# Myespsch1.net
KiCad netlist of a schematic drawn in Altium Designer
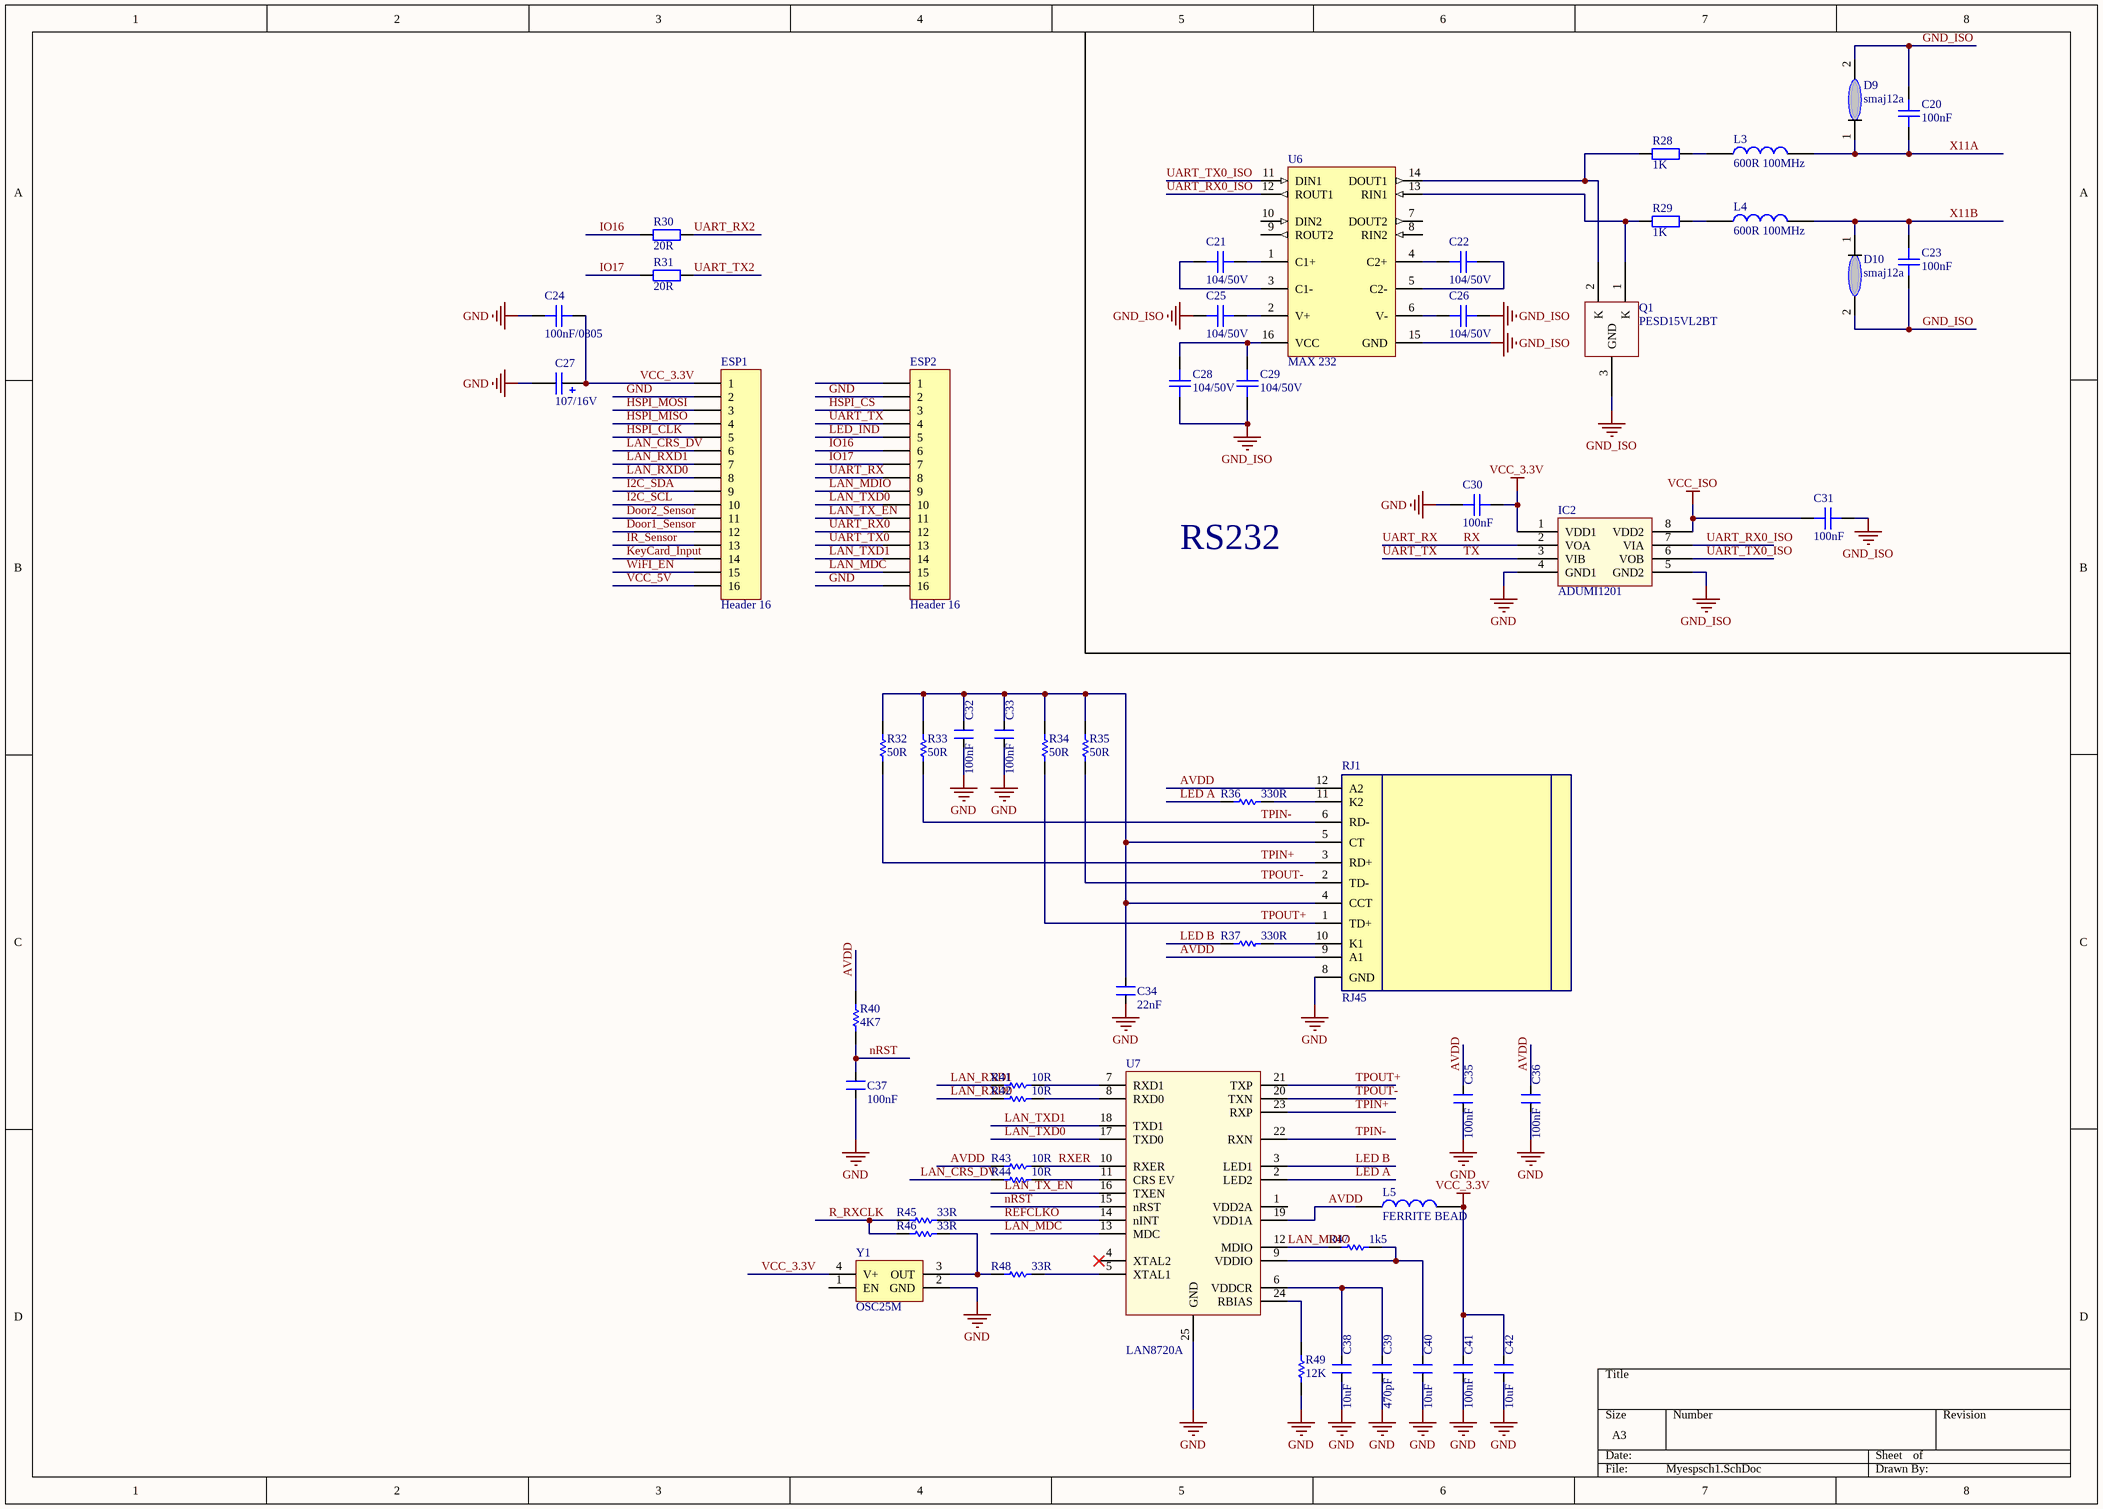
[diagram p0: Myespsch1.SchDoc]

(export (version "E")
  (design (tool "Eeschema 10.0.6"))
  (components
    (comp (ref "C20")
      (value "100nF")
      (footprint "CAPC-0603 (1608)")
      (fields (field (name "MPN") "C0603C104K5RACTU"))
      (libsource (lib "BYTECH_HW_LIB_2019 (1)") (part "C0603C104K5RACTU"))
    )
    (comp (ref "C21")
      (value "104/50V")
      (footprint "CAPC-0603 (1608)")
      (description "CAP CER 0.1uF 50V 10% X7R 0603")
      (fields (field (name "MPN") "C0603C104K5RACTU"))
      (libsource (lib "BYTECH_HW_LIB_2019 (1)") (part "C0603C104K5RACTU"))
    )
    (comp (ref "C22")
      (value "104/50V")
      (footprint "CAPC-0603 (1608)")
      (description "CAP CER 0.1uF 50V 10% X7R 0603")
      (fields (field (name "MPN") "C0603C104K5RACTU"))
      (libsource (lib "BYTECH_HW_LIB_2019 (1)") (part "C0603C104K5RACTU"))
    )
    (comp (ref "C23")
      (value "100nF")
      (footprint "CAPC-0603 (1608)")
      (fields (field (name "MPN") "C0603C104K5RACTU"))
      (libsource (lib "BYTECH_HW_LIB_2019 (1)") (part "C0603C104K5RACTU"))
    )
    (comp (ref "C24")
      (value "100nF/0805")
      (footprint "CAPC-0805 (2012)")
      (description "CAP CER 2.2uF 10% 10V X5R 0805")
      (fields (field (name "MPN") "0805C225K8PAC7800"))
      (libsource (lib "BYTECH_HW_LIB_2019 (1)") (part "0805C225K8PAC7800"))
    )
    (comp (ref "C25")
      (value "104/50V")
      (footprint "CAPC-0603 (1608)")
      (description "CAP CER 0.1uF 50V 10% X7R 0603")
      (fields (field (name "MPN") "C0603C104K5RACTU"))
      (libsource (lib "BYTECH_HW_LIB_2019 (1)") (part "C0603C104K5RACTU"))
    )
    (comp (ref "C26")
      (value "104/50V")
      (footprint "CAPC-0603 (1608)")
      (description "CAP CER 0.1uF 50V 10% X7R 0603")
      (fields (field (name "MPN") "C0603C104K5RACTU"))
      (libsource (lib "BYTECH_HW_LIB_2019 (1)") (part "C0603C104K5RACTU"))
    )
    (comp (ref "C27")
      (value "107/16V")
      (footprint "CAP_TANTAL_2917(7343-31)")
      (description "CAP TANT 100uF 16V 10% 2917")
      (fields (field (name "MPN") "TAJD107K016RNJ"))
      (libsource (lib "BYTECH_HW_LIB_2019 (1)") (part "TAJD107K016RNJ"))
    )
    (comp (ref "C28")
      (value "104/50V")
      (footprint "CAPC-0603 (1608)")
      (description "CAP CER 0.1uF 50V 10% X7R 0603")
      (fields (field (name "MPN") "C0603C104K5RACTU"))
      (libsource (lib "BYTECH_HW_LIB_2019 (1)") (part "C0603C104K5RACTU"))
    )
    (comp (ref "C29")
      (value "104/50V")
      (footprint "CAPC-0603 (1608)")
      (description "CAP CER 0.1uF 50V 10% X7R 0603")
      (fields (field (name "MPN") "C0603C104K5RACTU"))
      (libsource (lib "BYTECH_HW_LIB_2019 (1)") (part "C0603C104K5RACTU"))
    )
    (comp (ref "C30")
      (value "100nF")
      (footprint "CAPC-0603 (1608)")
      (fields (field (name "MPN") "C0603C104K5RACTU"))
      (libsource (lib "BYTECH_HW_LIB_2019 (1)") (part "C0603C104K5RACTU"))
    )
    (comp (ref "C31")
      (value "100nF")
      (footprint "CAPC-0603 (1608)")
      (fields (field (name "MPN") "C0603C104K5RACTU"))
      (libsource (lib "BYTECH_HW_LIB_2019 (1)") (part "C0603C104K5RACTU"))
    )
    (comp (ref "C32")
      (value "100nF")
      (footprint "CAPC-0805 (2012)")
      (description "CERAMIC CAP 0805")
      (libsource (lib "lpson") (part "CAP CERA 0805"))
    )
    (comp (ref "C33")
      (value "100nF")
      (footprint "CAPC-0805 (2012)")
      (description "CERAMIC CAP 0805")
      (libsource (lib "lpson") (part "CAP CERA 0805"))
    )
    (comp (ref "C34")
      (value "22nF")
      (footprint "CAPC-0805 (2012)")
      (description "CERAMIC CAP 0805")
      (libsource (lib "lpson") (part "CAP CERA 0805"))
    )
    (comp (ref "C35")
      (value "100nF")
      (footprint "CAPC-0805 (2012)")
      (description "CERAMIC CAP 0805")
      (libsource (lib "lpson") (part "CAP CERA 0805"))
    )
    (comp (ref "C36")
      (value "100nF")
      (footprint "CAPC-0805 (2012)")
      (description "CERAMIC CAP 0805")
      (libsource (lib "lpson") (part "CAP CERA 0805"))
    )
    (comp (ref "C37")
      (value "100nF")
      (footprint "RESC-0805 (2012)")
      (description "CERAMIC CAP 0805")
      (libsource (lib "lpson") (part "CAP CERA 0805"))
    )
    (comp (ref "C38")
      (value "10uF")
      (footprint "CAPC-0805 (2012)")
      (description "CERAMIC CAP 0805")
      (libsource (lib "lpson") (part "CAP CERA 0805"))
    )
    (comp (ref "C39")
      (value "470pF")
      (footprint "CAPC-0805 (2012)")
      (description "CERAMIC CAP 0805")
      (libsource (lib "lpson") (part "CAP CERA 0805"))
    )
    (comp (ref "C40")
      (value "10uF")
      (footprint "CAPC-0805 (2012)")
      (description "CERAMIC CAP 0805")
      (libsource (lib "lpson") (part "CAP CERA 0805"))
    )
    (comp (ref "C41")
      (value "100nF")
      (footprint "CAPC-0805 (2012)")
      (description "CERAMIC CAP 0805")
      (libsource (lib "lpson") (part "CAP CERA 0805"))
    )
    (comp (ref "C42")
      (value "10uF")
      (footprint "CAPC-0805 (2012)")
      (description "CERAMIC CAP 0805")
      (libsource (lib "lpson") (part "CAP CERA 0805"))
    )
    (comp (ref "D9")
      (value "smaj12a")
      (footprint "DIODE_DO214AC_SMA")
      (libsource (lib "Schlib1") (part "smaj12a"))
    )
    (comp (ref "D10")
      (value "smaj12a")
      (footprint "DIODE_DO214AC_SMA")
      (libsource (lib "") (part "smaj12a_1"))
    )
    (comp (ref "ESP1")
      (value "Header 16")
      (footprint "HDR1X16")
      (description "Header, 16-Pin")
      (fields (field (name "PUBLISHER") "Altium Limited"))
      (libsource (lib "My Library") (part "Header 16"))
    )
    (comp (ref "ESP2")
      (value "Header 16")
      (footprint "HDR1X16")
      (description "Header, 16-Pin")
      (fields (field (name "PUBLISHER") "Altium Limited"))
      (libsource (lib "My Library") (part "Header 16"))
    )
    (comp (ref "IC2") (value "ADUMI1201") (footprint "SOIC-8") (libsource (lib "Schlib1") (part "ADUMI1201")))
    (comp (ref "L3")
      (value "600R 100MHz")
      (footprint "IND-0603 (1608)")
      (description "FIXED IND 2.2UH 700MA 375 MOHM")
      (fields (field (name "MPN") "LQM18PN2R2MFHD") (field (name "MFR") "Murata Electronics"))
      (libsource (lib "BYTECH_HW_LIB_2019 (1)") (part "LQM18PN2R2MFHD"))
    )
    (comp (ref "L4")
      (value "600R 100MHz")
      (footprint "IND-0603 (1608)")
      (description "FIXED IND 2.2UH 700MA 375 MOHM")
      (fields (field (name "MPN") "LQM18PN2R2MFHD") (field (name "MFR") "Murata Electronics"))
      (libsource (lib "BYTECH_HW_LIB_2019 (1)") (part "LQM18PN2R2MFHD"))
    )
    (comp (ref "L5")
      (value "FERRITE BEAD")
      (footprint "IND-0805 (2012)")
      (description "IND-FERRITE BEAD 600 OHM 1LN 0805")
      (fields (field (name "MPN") "742792042"))
      (libsource (lib "BYTECH_HW_LIB_2019") (part "742792042"))
    )
    (comp (ref "Q1") (value "PESD15VL2BT") (footprint "SOT23") (libsource (lib "P1") (part "PESD15VL2BT")))
    (comp (ref "R28")
      (value "1K")
      (footprint "RESC-0603 (1608)")
      (description "RES SMD 4.7K OHM 1% 1/10W 0603")
      (fields (field (name "MPN") "RC0603FR-074K7L"))
      (libsource (lib "BYTECH_HW_LIB_2019 (1)") (part "RC0603FR-074K7L"))
    )
    (comp (ref "R29")
      (value "1K")
      (footprint "RESC-0603 (1608)")
      (description "RES SMD 4.7K OHM 1% 1/10W 0603")
      (fields (field (name "MPN") "RC0603FR-074K7L"))
      (libsource (lib "BYTECH_HW_LIB_2019 (1)") (part "RC0603FR-074K7L"))
    )
    (comp (ref "R30")
      (value "20R")
      (footprint "RESC-0603 (1608)")
      (description "RES SMD 20 OHM 1% 1/10W 0603")
      (fields (field (name "MPN") "CRCW060320R0FKEA"))
      (libsource (lib "BYTECH_HW_LIB_2019 (1)") (part "CRCW060320R0FKEA"))
    )
    (comp (ref "R31")
      (value "20R")
      (footprint "RESC-0603 (1608)")
      (description "RES SMD 20 OHM 1% 1/10W 0603")
      (fields (field (name "MPN") "CRCW060320R0FKEA"))
      (libsource (lib "BYTECH_HW_LIB_2019 (1)") (part "CRCW060320R0FKEA"))
    )
    (comp (ref "R32")
      (value "50R")
      (footprint "RESC-0805 (2012)")
      (description "RES SMD 249K OHM 1% 1/10W 0805")
      (fields
        (field (name "MANUFACTURER") "Yageo")
        (field (name "MANUFACTURER PART NUMBER") "RC0603FR-07249KL")
      )
      (libsource (lib "lpson") (part "RES-0805"))
    )
    (comp (ref "R33")
      (value "50R")
      (footprint "RESC-0805 (2012)")
      (description "RES SMD 249K OHM 1% 1/10W 0805")
      (fields
        (field (name "MANUFACTURER") "Yageo")
        (field (name "MANUFACTURER PART NUMBER") "RC0603FR-07249KL")
      )
      (libsource (lib "lpson") (part "RES-0805"))
    )
    (comp (ref "R34")
      (value "50R")
      (footprint "RESC-0805 (2012)")
      (description "RES SMD 249K OHM 1% 1/10W 0805")
      (fields
        (field (name "MANUFACTURER") "Yageo")
        (field (name "MANUFACTURER PART NUMBER") "RC0603FR-07249KL")
      )
      (libsource (lib "lpson") (part "RES-0805"))
    )
    (comp (ref "R35")
      (value "50R")
      (footprint "RESC-0805 (2012)")
      (description "RES SMD 249K OHM 1% 1/10W 0805")
      (fields
        (field (name "MANUFACTURER") "Yageo")
        (field (name "MANUFACTURER PART NUMBER") "RC0603FR-07249KL")
      )
      (libsource (lib "lpson") (part "RES-0805"))
    )
    (comp (ref "R36")
      (value "330R")
      (footprint "RESC-0805 (2012)")
      (description "RES SMD 249K OHM 1% 1/10W 0805")
      (fields
        (field (name "MANUFACTURER") "Yageo")
        (field (name "MANUFACTURER PART NUMBER") "RC0603FR-07249KL")
      )
      (libsource (lib "lpson") (part "RES-0805"))
    )
    (comp (ref "R37")
      (value "330R")
      (footprint "RESC-0805 (2012)")
      (description "RES SMD 249K OHM 1% 1/10W 0805")
      (fields
        (field (name "MANUFACTURER") "Yageo")
        (field (name "MANUFACTURER PART NUMBER") "RC0603FR-07249KL")
      )
      (libsource (lib "lpson") (part "RES-0805"))
    )
    (comp (ref "R40")
      (value "4K7")
      (footprint "RESC-0805 (2012)")
      (description "RES SMD 249K OHM 1% 1/10W 0805")
      (fields
        (field (name "MANUFACTURER") "Yageo")
        (field (name "MANUFACTURER PART NUMBER") "RC0603FR-07249KL")
      )
      (libsource (lib "lpson") (part "RES-0805"))
    )
    (comp (ref "R41")
      (value "10R")
      (footprint "RESC-0805 (2012)")
      (description "RES SMD 249K OHM 1% 1/10W 0805")
      (fields
        (field (name "MANUFACTURER") "Yageo")
        (field (name "MANUFACTURER PART NUMBER") "RC0603FR-07249KL")
      )
      (libsource (lib "lpson") (part "RES-0805"))
    )
    (comp (ref "R42")
      (value "10R")
      (footprint "RESC-0805 (2012)")
      (description "RES SMD 249K OHM 1% 1/10W 0805")
      (fields
        (field (name "MANUFACTURER") "Yageo")
        (field (name "MANUFACTURER PART NUMBER") "RC0603FR-07249KL")
      )
      (libsource (lib "lpson") (part "RES-0805"))
    )
    (comp (ref "R43")
      (value "10R")
      (footprint "RESC-0805 (2012)")
      (description "RES SMD 249K OHM 1% 1/10W 0805")
      (fields
        (field (name "MANUFACTURER") "Yageo")
        (field (name "MANUFACTURER PART NUMBER") "RC0603FR-07249KL")
      )
      (libsource (lib "lpson") (part "RES-0805"))
    )
    (comp (ref "R44")
      (value "10R")
      (footprint "RESC-0805 (2012)")
      (description "RES SMD 249K OHM 1% 1/10W 0805")
      (fields
        (field (name "MANUFACTURER") "Yageo")
        (field (name "MANUFACTURER PART NUMBER") "RC0603FR-07249KL")
      )
      (libsource (lib "lpson") (part "RES-0805"))
    )
    (comp (ref "R45")
      (value "33R")
      (footprint "RESC-0805 (2012)")
      (description "RES SMD 249K OHM 1% 1/10W 0805")
      (fields
        (field (name "MANUFACTURER") "Yageo")
        (field (name "MANUFACTURER PART NUMBER") "RC0603FR-07249KL")
      )
      (libsource (lib "lpson") (part "RES-0805"))
    )
    (comp (ref "R46")
      (value "33R")
      (footprint "RESC-0805 (2012)")
      (description "RES SMD 249K OHM 1% 1/10W 0805")
      (fields
        (field (name "MANUFACTURER") "Yageo")
        (field (name "MANUFACTURER PART NUMBER") "RC0603FR-07249KL")
      )
      (libsource (lib "lpson") (part "RES-0805"))
    )
    (comp (ref "R47")
      (value "1k5")
      (footprint "RESC-0805 (2012)")
      (description "RES SMD 249K OHM 1% 1/10W 0805")
      (fields
        (field (name "MANUFACTURER") "Yageo")
        (field (name "MANUFACTURER PART NUMBER") "RC0603FR-07249KL")
      )
      (libsource (lib "lpson") (part "RES-0805"))
    )
    (comp (ref "R48")
      (value "33R")
      (footprint "RESC-0805 (2012)")
      (description "RES SMD 249K OHM 1% 1/10W 0805")
      (fields
        (field (name "MANUFACTURER") "Yageo")
        (field (name "MANUFACTURER PART NUMBER") "RC0603FR-07249KL")
      )
      (libsource (lib "lpson") (part "RES-0805"))
    )
    (comp (ref "R49")
      (value "12K")
      (footprint "RESC-0805 (2012)")
      (description "RES SMD 249K OHM 1% 1/10W 0805")
      (fields
        (field (name "MANUFACTURER") "Yageo")
        (field (name "MANUFACTURER PART NUMBER") "RC0603FR-07249KL")
      )
      (libsource (lib "lpson") (part "RES-0805"))
    )
    (comp (ref "RJ1")
      (value "RJ45")
      (footprint "CON JR45")
      (libsource (lib "phanthanhlong3") (part "RJ45_2"))
    )
    (comp (ref "U6")
      (value "MAX 232")
      (footprint "SOIC-16")
      (description "IC DRVR/RCVR MULTCH RS232 16SOIC")
      (fields (field (name "MPN") "MAX3232CDRE4, MAX3232CDR"))
      (libsource (lib "BYTECH_HW_LIB_2019 (1)") (part "MAX3232CDRE4, MAX3232CDR"))
    )
    (comp (ref "U7")
      (value "LAN8720A")
      (footprint "24-VFQFN")
      (libsource (lib "phanthanhlong3") (part "LAN8720A"))
    )
    (comp (ref "Y1")
      (value "OSC25M")
      (footprint "CRYSTALL_SMD_3225")
      (description "XTAL OSC XO 25.0000MHZ CMOS SMD")
      (fields (field (name "MPN") "AU-25.000MBE-T"))
      (libsource (lib "BYTECH_HW_LIB_2019 (1)") (part "AU-25.000MBE-T"))
    )
  )
  (nets
    (net (code "1") (name "/AVDD") (class "Default")
      (node (ref "C35") (pin "1") (pinfunction "1_1") (pintype "passive"))
      (node (ref "C36") (pin "1") (pinfunction "1_1") (pintype "passive"))
      (node (ref "L5") (pin "1") (pinfunction "1_1") (pintype "passive"))
      (node (ref "R40") (pin "1") (pinfunction "1_1") (pintype "passive"))
      (node (ref "R43") (pin "2") (pinfunction "2_2") (pintype "passive"))
      (node (ref "RJ1") (pin "12") (pinfunction "A2_12") (pintype "passive"))
      (node (ref "RJ1") (pin "9") (pinfunction "A1_9") (pintype "passive"))
      (node (ref "U7") (pin "19") (pinfunction "VDD1A_19") (pintype "passive"))
    )
    (net (code "2") (name "/Door1_Sensor") (class "Default")
      (node (ref "ESP1") (pin "12") (pinfunction "12_12") (pintype "passive"))
    )
    (net (code "3") (name "/Door2_Sensor") (class "Default")
      (node (ref "ESP1") (pin "11") (pinfunction "11_11") (pintype "passive"))
    )
    (net (code "4") (name "/HSPI_CLK") (class "Default")
      (node (ref "ESP1") (pin "5") (pinfunction "5_5") (pintype "passive"))
    )
    (net (code "5") (name "/HSPI_CS") (class "Default")
      (node (ref "ESP2") (pin "3") (pinfunction "3_3") (pintype "passive"))
    )
    (net (code "6") (name "/HSPI_MISO") (class "Default")
      (node (ref "ESP1") (pin "4") (pinfunction "4_4") (pintype "passive"))
    )
    (net (code "7") (name "/HSPI_MOSI") (class "Default")
      (node (ref "ESP1") (pin "3") (pinfunction "3_3") (pintype "passive"))
    )
    (net (code "8") (name "/I2C_SCL") (class "Default")
      (node (ref "ESP1") (pin "10") (pinfunction "10_10") (pintype "passive"))
    )
    (net (code "9") (name "/I2C_SDA") (class "Default")
      (node (ref "ESP1") (pin "9") (pinfunction "9_9") (pintype "passive"))
    )
    (net (code "10") (name "/IO16") (class "Default")
      (node (ref "ESP2") (pin "6") (pinfunction "6_6") (pintype "passive"))
      (node (ref "R30") (pin "1") (pinfunction "1_1") (pintype "passive"))
    )
    (net (code "11") (name "/IO17") (class "Default")
      (node (ref "ESP2") (pin "7") (pinfunction "7_7") (pintype "passive"))
      (node (ref "R31") (pin "1") (pinfunction "1_1") (pintype "passive"))
    )
    (net (code "12") (name "/IR_Sensor") (class "Default")
      (node (ref "ESP1") (pin "13") (pinfunction "13_13") (pintype "passive"))
    )
    (net (code "13") (name "/KeyCard_Input") (class "Default")
      (node (ref "ESP1") (pin "14") (pinfunction "14_14") (pintype "passive"))
    )
    (net (code "14") (name "/LAN_CRS_DV") (class "Default")
      (node (ref "ESP1") (pin "6") (pinfunction "6_6") (pintype "passive"))
      (node (ref "R44") (pin "2") (pinfunction "2_2") (pintype "passive"))
    )
    (net (code "15") (name "/LAN_MDC") (class "Default")
      (node (ref "ESP2") (pin "15") (pinfunction "15_15") (pintype "passive"))
      (node (ref "U7") (pin "13") (pinfunction "MDC_13") (pintype "passive"))
    )
    (net (code "16") (name "/LAN_MDIO") (class "Default")
      (node (ref "ESP2") (pin "9") (pinfunction "9_9") (pintype "passive"))
      (node (ref "R47") (pin "2") (pinfunction "2_2") (pintype "passive"))
      (node (ref "U7") (pin "12") (pinfunction "MDIO_12") (pintype "passive"))
    )
    (net (code "17") (name "/LAN_RXD0") (class "Default")
      (node (ref "ESP1") (pin "8") (pinfunction "8_8") (pintype "passive"))
      (node (ref "R42") (pin "2") (pinfunction "2_2") (pintype "passive"))
    )
    (net (code "18") (name "/LAN_RXD1") (class "Default")
      (node (ref "ESP1") (pin "7") (pinfunction "7_7") (pintype "passive"))
      (node (ref "R41") (pin "2") (pinfunction "2_2") (pintype "passive"))
    )
    (net (code "19") (name "/LAN_TXD0") (class "Default")
      (node (ref "ESP2") (pin "10") (pinfunction "10_10") (pintype "passive"))
      (node (ref "U7") (pin "17") (pinfunction "TXD0_17") (pintype "passive"))
    )
    (net (code "20") (name "/LAN_TXD1") (class "Default")
      (node (ref "ESP2") (pin "14") (pinfunction "14_14") (pintype "passive"))
      (node (ref "U7") (pin "18") (pinfunction "TXD1_18") (pintype "passive"))
    )
    (net (code "21") (name "/LAN_TX_EN") (class "Default")
      (node (ref "ESP2") (pin "11") (pinfunction "11_11") (pintype "passive"))
      (node (ref "U7") (pin "16") (pinfunction "TXEN_16") (pintype "passive"))
    )
    (net (code "22") (name "/LED A") (class "Default")
      (node (ref "R36") (pin "1") (pinfunction "1_1") (pintype "passive"))
      (node (ref "U7") (pin "2") (pinfunction "LED2_2") (pintype "passive"))
    )
    (net (code "23") (name "/LED B") (class "Default")
      (node (ref "R37") (pin "1") (pinfunction "1_1") (pintype "passive"))
      (node (ref "U7") (pin "3") (pinfunction "LED1_3") (pintype "passive"))
    )
    (net (code "24") (name "/LED_IND") (class "Default")
      (node (ref "ESP2") (pin "5") (pinfunction "5_5") (pintype "passive"))
    )
    (net (code "25") (name "/REFCLKO") (class "Default")
      (node (ref "R45") (pin "1") (pinfunction "1_1") (pintype "passive"))
      (node (ref "U7") (pin "14") (pinfunction "nINT_14") (pintype "passive"))
    )
    (net (code "26") (name "/RX") (class "Default")
      (node (ref "ESP2") (pin "8") (pinfunction "8_8") (pintype "passive"))
      (node (ref "IC2") (pin "2") (pinfunction "VOA_2") (pintype "passive"))
    )
    (net (code "27") (name "/RXER") (class "Default")
      (node (ref "R43") (pin "1") (pinfunction "1_1") (pintype "passive"))
      (node (ref "U7") (pin "10") (pinfunction "RXER_10") (pintype "passive"))
    )
    (net (code "28") (name "/R_RXCLK") (class "Default")
      (node (ref "R45") (pin "2") (pinfunction "2_2") (pintype "passive"))
      (node (ref "R46") (pin "2") (pinfunction "2_2") (pintype "passive"))
    )
    (net (code "29") (name "/TPIN+") (class "Default")
      (node (ref "R32") (pin "1") (pinfunction "1_1") (pintype "passive"))
      (node (ref "RJ1") (pin "3") (pinfunction "RD+_3") (pintype "passive"))
      (node (ref "U7") (pin "23") (pinfunction "RXP_23") (pintype "passive"))
    )
    (net (code "30") (name "/TPIN-") (class "Default")
      (node (ref "R33") (pin "1") (pinfunction "1_1") (pintype "passive"))
      (node (ref "RJ1") (pin "6") (pinfunction "RD-_6") (pintype "passive"))
      (node (ref "U7") (pin "22") (pinfunction "RXN_22") (pintype "passive"))
    )
    (net (code "31") (name "/TPOUT+") (class "Default")
      (node (ref "R34") (pin "1") (pinfunction "1_1") (pintype "passive"))
      (node (ref "RJ1") (pin "1") (pinfunction "TD+_1") (pintype "passive"))
      (node (ref "U7") (pin "21") (pinfunction "TXP_21") (pintype "passive"))
    )
    (net (code "32") (name "/TPOUT-") (class "Default")
      (node (ref "R35") (pin "1") (pinfunction "1_1") (pintype "passive"))
      (node (ref "RJ1") (pin "2") (pinfunction "TD-_2") (pintype "passive"))
      (node (ref "U7") (pin "20") (pinfunction "TXN_20") (pintype "passive"))
    )
    (net (code "33") (name "/TX") (class "Default")
      (node (ref "ESP2") (pin "4") (pinfunction "4_4") (pintype "passive"))
      (node (ref "IC2") (pin "3") (pinfunction "VIB_3") (pintype "passive"))
    )
    (net (code "34") (name "/UART_RX0") (class "Default")
      (node (ref "ESP2") (pin "12") (pinfunction "12_12") (pintype "passive"))
    )
    (net (code "35") (name "/UART_RX0_ISO") (class "Default")
      (node (ref "IC2") (pin "7") (pinfunction "VIA_7") (pintype "passive"))
      (node (ref "U6") (pin "12") (pinfunction "ROUT1_12") (pintype "output"))
    )
    (net (code "36") (name "/UART_RX2") (class "Default")
      (node (ref "R30") (pin "2") (pinfunction "2_2") (pintype "passive"))
    )
    (net (code "37") (name "/UART_TX0") (class "Default")
      (node (ref "ESP2") (pin "13") (pinfunction "13_13") (pintype "passive"))
    )
    (net (code "38") (name "/UART_TX0_ISO") (class "Default")
      (node (ref "IC2") (pin "6") (pinfunction "VOB_6") (pintype "passive"))
      (node (ref "U6") (pin "11") (pinfunction "DIN1_11") (pintype "input"))
    )
    (net (code "39") (name "/UART_TX2") (class "Default")
      (node (ref "R31") (pin "2") (pinfunction "2_2") (pintype "passive"))
    )
    (net (code "40") (name "/VCC_5V") (class "Default")
      (node (ref "ESP1") (pin "16") (pinfunction "16_16") (pintype "passive"))
    )
    (net (code "41") (name "/WiFI_EN") (class "Default")
      (node (ref "ESP1") (pin "15") (pinfunction "15_15") (pintype "passive"))
    )
    (net (code "42") (name "/X11A") (class "Default")
      (node (ref "C20") (pin "2") (pinfunction "2_2") (pintype "passive"))
      (node (ref "D9") (pin "1") (pintype "passive"))
      (node (ref "L3") (pin "2") (pinfunction "2_2") (pintype "passive"))
    )
    (net (code "43") (name "/X11B") (class "Default")
      (node (ref "C23") (pin "1") (pinfunction "1_1") (pintype "passive"))
      (node (ref "D10") (pin "1") (pintype "passive"))
      (node (ref "L4") (pin "2") (pinfunction "2_2") (pintype "passive"))
    )
    (net (code "44") (name "/nRST") (class "Default")
      (node (ref "C37") (pin "1") (pinfunction "1_1") (pintype "passive"))
      (node (ref "R40") (pin "2") (pinfunction "2_2") (pintype "passive"))
      (node (ref "U7") (pin "15") (pinfunction "nRST_15") (pintype "passive"))
    )
    (net (code "45") (name "GND") (class "Default")
      (node (ref "C24") (pin "1") (pinfunction "1_1") (pintype "passive"))
      (node (ref "C27") (pin "2") (pinfunction "2_2") (pintype "passive"))
      (node (ref "C30") (pin "2") (pinfunction "2_2") (pintype "passive"))
      (node (ref "C32") (pin "2") (pinfunction "2_2") (pintype "passive"))
      (node (ref "C33") (pin "2") (pinfunction "2_2") (pintype "passive"))
      (node (ref "C34") (pin "2") (pinfunction "2_2") (pintype "passive"))
      (node (ref "C35") (pin "2") (pinfunction "2_2") (pintype "passive"))
      (node (ref "C36") (pin "2") (pinfunction "2_2") (pintype "passive"))
      (node (ref "C37") (pin "2") (pinfunction "2_2") (pintype "passive"))
      (node (ref "C38") (pin "2") (pinfunction "2_2") (pintype "passive"))
      (node (ref "C39") (pin "2") (pinfunction "2_2") (pintype "passive"))
      (node (ref "C40") (pin "2") (pinfunction "2_2") (pintype "passive"))
      (node (ref "C41") (pin "2") (pinfunction "2_2") (pintype "passive"))
      (node (ref "C42") (pin "2") (pinfunction "2_2") (pintype "passive"))
      (node (ref "ESP1") (pin "2") (pinfunction "2_2") (pintype "passive"))
      (node (ref "ESP2") (pin "16") (pinfunction "16_16") (pintype "passive"))
      (node (ref "ESP2") (pin "2") (pinfunction "2_2") (pintype "passive"))
      (node (ref "IC2") (pin "4") (pinfunction "GND1_4") (pintype "passive"))
      (node (ref "R49") (pin "1") (pinfunction "1_1") (pintype "passive"))
      (node (ref "RJ1") (pin "8") (pinfunction "GND_8") (pintype "passive"))
      (node (ref "U7") (pin "25") (pinfunction "GND_25") (pintype "passive"))
      (node (ref "Y1") (pin "2") (pinfunction "GND_2") (pintype "passive"))
    )
    (net (code "46") (name "GND_ISO") (class "Default")
      (node (ref "C20") (pin "1") (pinfunction "1_1") (pintype "passive"))
      (node (ref "C23") (pin "2") (pinfunction "2_2") (pintype "passive"))
      (node (ref "C25") (pin "1") (pinfunction "1_1") (pintype "passive"))
      (node (ref "C26") (pin "2") (pinfunction "2_2") (pintype "passive"))
      (node (ref "C28") (pin "1") (pinfunction "1_1") (pintype "passive"))
      (node (ref "C29") (pin "1") (pinfunction "1_1") (pintype "passive"))
      (node (ref "C31") (pin "1") (pinfunction "1_1") (pintype "passive"))
      (node (ref "D10") (pin "2") (pintype "passive"))
      (node (ref "D9") (pin "2") (pintype "passive"))
      (node (ref "IC2") (pin "5") (pinfunction "GND2_5") (pintype "passive"))
      (node (ref "Q1") (pin "3") (pinfunction "GND_3") (pintype "passive"))
      (node (ref "U6") (pin "15") (pinfunction "GND_15") (pintype "power_in"))
    )
    (net (code "47") (name "Net-(L3-Pad1)") (class "Default")
      (node (ref "L3") (pin "1") (pinfunction "1_1") (pintype "passive"))
      (node (ref "R28") (pin "2") (pinfunction "2_2") (pintype "passive"))
    )
    (net (code "48") (name "Net-(L4-Pad1)") (class "Default")
      (node (ref "L4") (pin "1") (pinfunction "1_1") (pintype "passive"))
      (node (ref "R29") (pin "2") (pinfunction "2_2") (pintype "passive"))
    )
    (net (code "49") (name "Net-(RJ1-CCT)") (class "Default")
      (node (ref "C32") (pin "1") (pinfunction "1_1") (pintype "passive"))
      (node (ref "C33") (pin "1") (pinfunction "1_1") (pintype "passive"))
      (node (ref "C34") (pin "1") (pinfunction "1_1") (pintype "passive"))
      (node (ref "R32") (pin "2") (pinfunction "2_2") (pintype "passive"))
      (node (ref "R33") (pin "2") (pinfunction "2_2") (pintype "passive"))
      (node (ref "R34") (pin "2") (pinfunction "2_2") (pintype "passive"))
      (node (ref "R35") (pin "2") (pinfunction "2_2") (pintype "passive"))
      (node (ref "RJ1") (pin "4") (pinfunction "CCT_4") (pintype "passive"))
      (node (ref "RJ1") (pin "5") (pinfunction "CT_5") (pintype "passive"))
    )
    (net (code "50") (name "Net-(RJ1-K1)") (class "Default")
      (node (ref "R37") (pin "2") (pinfunction "2_2") (pintype "passive"))
      (node (ref "RJ1") (pin "10") (pinfunction "K1_10") (pintype "passive"))
    )
    (net (code "51") (name "Net-(RJ1-K2)") (class "Default")
      (node (ref "R36") (pin "2") (pinfunction "2_2") (pintype "passive"))
      (node (ref "RJ1") (pin "11") (pinfunction "K2_11") (pintype "passive"))
    )
    (net (code "52") (name "Net-(U6-C1+)") (class "Default")
      (node (ref "C21") (pin "2") (pinfunction "2_2") (pintype "passive"))
      (node (ref "U6") (pin "1") (pinfunction "C1+_1") (pintype "passive"))
    )
    (net (code "53") (name "Net-(U6-C1-)") (class "Default")
      (node (ref "C21") (pin "1") (pinfunction "1_1") (pintype "passive"))
      (node (ref "U6") (pin "3") (pinfunction "C1-_3") (pintype "passive"))
    )
    (net (code "54") (name "Net-(U6-C2+)") (class "Default")
      (node (ref "C22") (pin "1") (pinfunction "1_1") (pintype "passive"))
      (node (ref "U6") (pin "4") (pinfunction "C2+_4") (pintype "passive"))
    )
    (net (code "55") (name "Net-(U6-C2-)") (class "Default")
      (node (ref "C22") (pin "2") (pinfunction "2_2") (pintype "passive"))
      (node (ref "U6") (pin "5") (pinfunction "C2-_5") (pintype "passive"))
    )
    (net (code "56") (name "Net-(U6-DOUT1)") (class "Default")
      (node (ref "Q1") (pin "2") (pinfunction "K_2") (pintype "passive"))
      (node (ref "R28") (pin "1") (pinfunction "1_1") (pintype "passive"))
      (node (ref "U6") (pin "14") (pinfunction "DOUT1_14") (pintype "output"))
    )
    (net (code "57") (name "Net-(U6-RIN1)") (class "Default")
      (node (ref "Q1") (pin "1") (pinfunction "K_1") (pintype "passive"))
      (node (ref "R29") (pin "1") (pinfunction "1_1") (pintype "passive"))
      (node (ref "U6") (pin "13") (pinfunction "RIN1_13") (pintype "input"))
    )
    (net (code "58") (name "Net-(U6-V+)") (class "Default")
      (node (ref "C25") (pin "2") (pinfunction "2_2") (pintype "passive"))
      (node (ref "U6") (pin "2") (pinfunction "V+_2") (pintype "power_in"))
    )
    (net (code "59") (name "Net-(U6-V-)") (class "Default")
      (node (ref "C26") (pin "1") (pinfunction "1_1") (pintype "passive"))
      (node (ref "U6") (pin "6") (pinfunction "V-_6") (pintype "power_in"))
    )
    (net (code "60") (name "Net-(U6-VCC)") (class "Default")
      (node (ref "C28") (pin "2") (pinfunction "2_2") (pintype "passive"))
      (node (ref "C29") (pin "2") (pinfunction "2_2") (pintype "passive"))
      (node (ref "U6") (pin "16") (pinfunction "VCC_16") (pintype "power_in"))
    )
    (net (code "61") (name "Net-(U7-CRS_EV)") (class "Default")
      (node (ref "R44") (pin "1") (pinfunction "1_1") (pintype "passive"))
      (node (ref "U7") (pin "11") (pinfunction "CRS_EV_11") (pintype "passive"))
    )
    (net (code "62") (name "Net-(U7-RBIAS)") (class "Default")
      (node (ref "R49") (pin "2") (pinfunction "2_2") (pintype "passive"))
      (node (ref "U7") (pin "24") (pinfunction "RBIAS_24") (pintype "passive"))
    )
    (net (code "63") (name "Net-(U7-RXD0)") (class "Default")
      (node (ref "R42") (pin "1") (pinfunction "1_1") (pintype "passive"))
      (node (ref "U7") (pin "8") (pinfunction "RXD0_8") (pintype "passive"))
    )
    (net (code "64") (name "Net-(U7-RXD1)") (class "Default")
      (node (ref "R41") (pin "1") (pinfunction "1_1") (pintype "passive"))
      (node (ref "U7") (pin "7") (pinfunction "RXD1_7") (pintype "passive"))
    )
    (net (code "65") (name "Net-(U7-VDDCR)") (class "Default")
      (node (ref "C38") (pin "1") (pinfunction "1_1") (pintype "passive"))
      (node (ref "C39") (pin "1") (pinfunction "1_1") (pintype "passive"))
      (node (ref "U7") (pin "6") (pinfunction "VDDCR_6") (pintype "passive"))
    )
    (net (code "66") (name "Net-(U7-VDDIO)") (class "Default")
      (node (ref "C40") (pin "1") (pinfunction "1_1") (pintype "passive"))
      (node (ref "R47") (pin "1") (pinfunction "1_1") (pintype "passive"))
      (node (ref "U7") (pin "9") (pinfunction "VDDIO_9") (pintype "passive"))
    )
    (net (code "67") (name "Net-(U7-XTAL1)") (class "Default")
      (node (ref "R48") (pin "1") (pinfunction "1_1") (pintype "passive"))
      (node (ref "U7") (pin "5") (pinfunction "XTAL1_5") (pintype "passive"))
    )
    (net (code "68") (name "Net-(Y1-OUT)") (class "Default")
      (node (ref "R46") (pin "1") (pinfunction "1_1") (pintype "passive"))
      (node (ref "R48") (pin "2") (pinfunction "2_2") (pintype "passive"))
      (node (ref "Y1") (pin "3") (pinfunction "OUT_3") (pintype "passive"))
    )
    (net (code "69") (name "VCC_3.3V") (class "Default")
      (node (ref "C24") (pin "2") (pinfunction "2_2") (pintype "passive"))
      (node (ref "C27") (pin "1") (pinfunction "1_1") (pintype "passive"))
      (node (ref "C30") (pin "1") (pinfunction "1_1") (pintype "passive"))
      (node (ref "C41") (pin "1") (pinfunction "1_1") (pintype "passive"))
      (node (ref "C42") (pin "1") (pinfunction "1_1") (pintype "passive"))
      (node (ref "ESP1") (pin "1") (pinfunction "1_1") (pintype "passive"))
      (node (ref "IC2") (pin "1") (pinfunction "VDD1_1") (pintype "passive"))
      (node (ref "L5") (pin "2") (pinfunction "2_2") (pintype "passive"))
      (node (ref "Y1") (pin "4") (pinfunction "V+_4") (pintype "passive"))
    )
    (net (code "70") (name "VCC_ISO") (class "Default")
      (node (ref "C31") (pin "2") (pinfunction "2_2") (pintype "passive"))
      (node (ref "IC2") (pin "8") (pinfunction "VDD2_8") (pintype "passive"))
    )
    (net (code "71") (name "unconnected-(ESP2-Pad1)") (class "Default")
      (node (ref "ESP2") (pin "1") (pinfunction "1_1") (pintype "passive"))
    )
    (net (code "72") (name "unconnected-(U6-DIN2-Pad10)") (class "Default")
      (node (ref "U6") (pin "10") (pinfunction "DIN2_10") (pintype "input"))
    )
    (net (code "73") (name "unconnected-(U6-DOUT2-Pad7)") (class "Default")
      (node (ref "U6") (pin "7") (pinfunction "DOUT2_7") (pintype "output"))
    )
    (net (code "74") (name "unconnected-(U6-RIN2-Pad8)") (class "Default")
      (node (ref "U6") (pin "8") (pinfunction "RIN2_8") (pintype "input"))
    )
    (net (code "75") (name "unconnected-(U6-ROUT2-Pad9)") (class "Default")
      (node (ref "U6") (pin "9") (pinfunction "ROUT2_9") (pintype "output"))
    )
    (net (code "76") (name "unconnected-(U7-VDD2A-Pad1)") (class "Default")
      (node (ref "U7") (pin "1") (pinfunction "VDD2A_1") (pintype "passive"))
    )
    (net (code "77") (name "unconnected-(U7-XTAL2-Pad4)") (class "Default")
      (node (ref "U7") (pin "4") (pinfunction "XTAL2_4") (pintype "passive+no_connect"))
    )
    (net (code "78") (name "unconnected-(Y1-EN-Pad1)") (class "Default")
      (node (ref "Y1") (pin "1") (pinfunction "EN_1") (pintype "passive"))
    )
  )
)
